# 2017_Ozone.net
KiCad netlist of a schematic drawn in Altium Designer
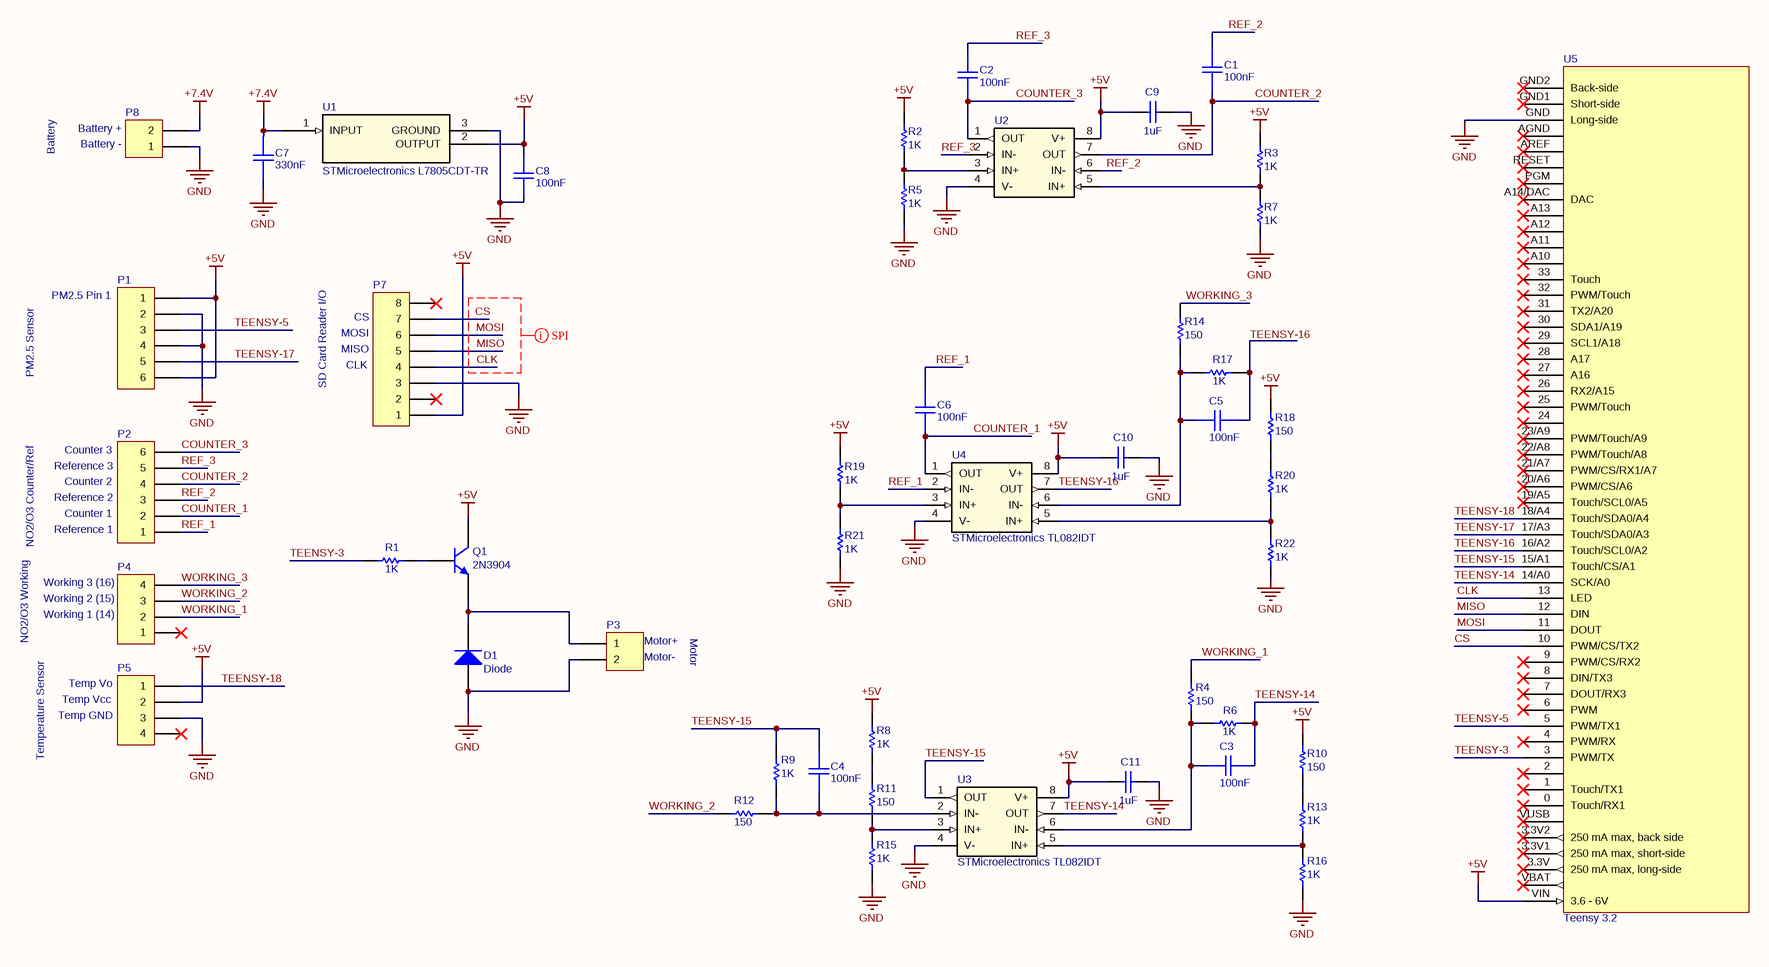
[diagram p0: 2017_Ozone.SchDoc]

(export (version "E")
  (design (tool "Eeschema 10.0.6"))
  (components
    (comp (ref "C1")
      (value "100nF")
      (footprint "Yageo CC0603ZRY5V9BB104 (1608)")
      (description "100 nF Capacitor")
      (fields (field (name "MANUFACTURER_PART_NUMBER") "CC0603ZRY5V9BB104"))
      (libsource (lib "2017_Ozone") (part "Yageo CC0603ZRY5V9BB104"))
    )
    (comp (ref "C2")
      (value "100nF")
      (footprint "Yageo CC0603ZRY5V9BB104 (1608)")
      (description "100 nF Capacitor")
      (fields (field (name "MANUFACTURER_PART_NUMBER") "CC0603ZRY5V9BB104"))
      (libsource (lib "2017_Ozone") (part "Yageo CC0603ZRY5V9BB104"))
    )
    (comp (ref "C3")
      (value "100nF")
      (footprint "Yageo CC0603ZRY5V9BB104 (1608)")
      (description "100 nF Capacitor")
      (fields (field (name "MANUFACTURER_PART_NUMBER") "CC0603ZRY5V9BB104"))
      (libsource (lib "2017_Ozone") (part "Yageo CC0603ZRY5V9BB104"))
    )
    (comp (ref "C4")
      (value "100nF")
      (footprint "Yageo CC0603ZRY5V9BB104 (1608)")
      (description "100 nF Capacitor")
      (fields (field (name "MANUFACTURER_PART_NUMBER") "CC0603ZRY5V9BB104"))
      (libsource (lib "2017_Ozone") (part "Yageo CC0603ZRY5V9BB104"))
    )
    (comp (ref "C5")
      (value "100nF")
      (footprint "Yageo CC0603ZRY5V9BB104 (1608)")
      (description "100 nF Capacitor")
      (fields (field (name "MANUFACTURER_PART_NUMBER") "CC0603ZRY5V9BB104"))
      (libsource (lib "2017_Ozone") (part "Yageo CC0603ZRY5V9BB104"))
    )
    (comp (ref "C6")
      (value "100nF")
      (footprint "Yageo CC0603ZRY5V9BB104 (1608)")
      (description "100 nF Capacitor")
      (fields (field (name "MANUFACTURER_PART_NUMBER") "CC0603ZRY5V9BB104"))
      (libsource (lib "2017_Ozone") (part "Yageo CC0603ZRY5V9BB104"))
    )
    (comp (ref "C7")
      (value "330nF")
      (footprint "Yageo CC0603ZRY5V9BB104 (1608)")
      (description "330nF Capacitor")
      (libsource (lib "") (part "Yageo CC0603ZRY5V9BB104_1"))
    )
    (comp (ref "C8")
      (value "100nF")
      (footprint "Yageo CC0603ZRY5V9BB104 (1608)")
      (description "100 nF Capacitor")
      (fields (field (name "MANUFACTURER_PART_NUMBER") "CC0603ZRY5V9BB104"))
      (libsource (lib "") (part "Yageo CC0603ZRY5V9BB104_1"))
    )
    (comp (ref "C9")
      (value "1uF")
      (footprint "Yageo CC0603ZRY5V9BB104 (1608)")
      (description "Capacitor")
      (fields (field (name "Comment") "Cap") (field (name "PUBLISHER") "Altium Limited"))
      (libsource (lib "Miscellaneous Devices") (part "Cap"))
    )
    (comp (ref "C10")
      (value "1uF")
      (footprint "Yageo CC0603ZRY5V9BB104 (1608)")
      (description "Capacitor")
      (fields (field (name "Comment") "Cap") (field (name "PUBLISHER") "Altium Limited"))
      (libsource (lib "Miscellaneous Devices") (part "Cap"))
    )
    (comp (ref "C11")
      (value "1uF")
      (footprint "Yageo CC0603ZRY5V9BB104 (1608)")
      (description "Capacitor")
      (fields (field (name "Comment") "Cap") (field (name "PUBLISHER") "Altium Limited"))
      (libsource (lib "Miscellaneous Devices") (part "Cap"))
    )
    (comp (ref "D1")
      (value "Diode")
      (footprint "SOT95P240X120-3N")
      (description "Default Diode")
      (fields (field (name "PUBLISHER") "Altium Limited"))
      (libsource (lib "Miscellaneous Devices") (part "Diode"))
    )
    (comp (ref "P1")
      (value "Molex 0430450600")
      (footprint "Molex 0430450600")
      (libsource (lib "") (part "Molex 0430450600_1"))
    )
    (comp (ref "P2")
      (value "Molex 0430450600")
      (footprint "Molex 0430450600")
      (libsource (lib "2017_Ozone") (part "Molex 0430450600"))
    )
    (comp (ref "P3")
      (value "Molex 0430450200")
      (footprint "Molex 0430450200")
      (libsource (lib "2017_Ozone") (part "Molex 0430450200"))
    )
    (comp (ref "P4")
      (value "Molex 0430450400")
      (footprint "Molex 0430450400")
      (libsource (lib "") (part "Molex 0430450400_1"))
    )
    (comp (ref "P5")
      (value "Molex 0430450400")
      (footprint "Molex 0430450400")
      (libsource (lib "2017_Ozone") (part "Molex 0430450400"))
    )
    (comp (ref "P7")
      (value "Molex 0430450800")
      (footprint "Molex 0430450800")
      (libsource (lib "2017_Ozone") (part "Molex 0430450800"))
    )
    (comp (ref "P8")
      (value "Molex 0430450200")
      (footprint "Molex 0430450200")
      (libsource (lib "") (part "Molex 0430450200_1"))
    )
    (comp (ref "Q1")
      (value "2N3904")
      (footprint "TO92")
      (description "NPN General Purpose Amplifier")
      (fields (field (name "PUBLISHER") "Altium Limited"))
      (libsource (lib "Miscellaneous Devices") (part "2N3904"))
    )
    (comp (ref "R1")
      (value "1K")
      (footprint "Panasonic ERJ-Series (1608)")
      (description "Resistor")
      (fields (field (name "Comment") "1k Ohm") (field (name "PUBLISHER") "Altium Limited"))
      (libsource (lib "") (part "1k Ohm_1"))
    )
    (comp (ref "R2")
      (value "1K")
      (footprint "Panasonic ERJ-Series (1608)")
      (description "Resistor")
      (fields (field (name "Comment") "1k Ohm") (field (name "PUBLISHER") "Altium Limited"))
      (libsource (lib "2017_Ozone") (part "1k Ohm"))
    )
    (comp (ref "R3")
      (value "1K")
      (footprint "Panasonic ERJ-Series (1608)")
      (description "Resistor")
      (fields (field (name "Comment") "1k Ohm") (field (name "PUBLISHER") "Altium Limited"))
      (libsource (lib "2017_Ozone") (part "1k Ohm"))
    )
    (comp (ref "R4")
      (value "150")
      (footprint "Panasonic ERJ-Series (1608)")
      (description "Resistor")
      (fields (field (name "Comment") "150 Ohm") (field (name "PUBLISHER") "Altium Limited"))
      (libsource (lib "2017_Ozone") (part "150 Ohm"))
    )
    (comp (ref "R5")
      (value "1K")
      (footprint "Panasonic ERJ-Series (1608)")
      (description "Resistor")
      (fields (field (name "Comment") "1k Ohm") (field (name "PUBLISHER") "Altium Limited"))
      (libsource (lib "2017_Ozone") (part "1k Ohm"))
    )
    (comp (ref "R6")
      (value "1K")
      (footprint "Panasonic ERJ-Series (1608)")
      (description "Resistor")
      (fields (field (name "Comment") "1k Ohm") (field (name "PUBLISHER") "Altium Limited"))
      (libsource (lib "2017_Ozone") (part "1k Ohm"))
    )
    (comp (ref "R7")
      (value "1K")
      (footprint "Panasonic ERJ-Series (1608)")
      (description "Resistor")
      (fields (field (name "Comment") "1k Ohm") (field (name "PUBLISHER") "Altium Limited"))
      (libsource (lib "2017_Ozone") (part "1k Ohm"))
    )
    (comp (ref "R8")
      (value "1K")
      (footprint "Panasonic ERJ-Series (1608)")
      (description "1k Ohm Resistor")
      (fields (field (name "Comment") "Panasonic ERJ-3GEYJ102V") (field (name "PUBLISHER") "Altium Limited"))
      (libsource (lib "2017_Ozone") (part "Panasonic ERJ-3GEYJ102V"))
    )
    (comp (ref "R9")
      (value "1K")
      (footprint "Panasonic ERJ-Series (1608)")
      (description "Resistor")
      (fields (field (name "Comment") "1k Ohm") (field (name "PUBLISHER") "Altium Limited"))
      (libsource (lib "2017_Ozone") (part "1k Ohm"))
    )
    (comp (ref "R10")
      (value "150")
      (footprint "Panasonic ERJ-Series (1608)")
      (description "Resistor")
      (fields (field (name "Comment") "150 Ohm") (field (name "PUBLISHER") "Altium Limited"))
      (libsource (lib "2017_Ozone") (part "150 Ohm"))
    )
    (comp (ref "R11")
      (value "150")
      (footprint "Panasonic ERJ-Series (1608)")
      (description "150 Ohm Resistor")
      (fields (field (name "Comment") "150 Ohm") (field (name "PUBLISHER") "Altium Limited"))
      (libsource (lib "") (part "150 Ohm_1"))
    )
    (comp (ref "R12")
      (value "150")
      (footprint "Panasonic ERJ-Series (1608)")
      (description "Resistor")
      (fields (field (name "Comment") "150 Ohm") (field (name "PUBLISHER") "Altium Limited"))
      (libsource (lib "2017_Ozone") (part "150 Ohm"))
    )
    (comp (ref "R13")
      (value "1K")
      (footprint "Panasonic ERJ-Series (1608)")
      (description "Resistor")
      (fields (field (name "Comment") "1k Ohm") (field (name "PUBLISHER") "Altium Limited"))
      (libsource (lib "2017_Ozone") (part "1k Ohm"))
    )
    (comp (ref "R14")
      (value "150")
      (footprint "Panasonic ERJ-Series (1608)")
      (description "Resistor")
      (fields (field (name "Comment") "150 Ohm") (field (name "PUBLISHER") "Altium Limited"))
      (libsource (lib "2017_Ozone") (part "150 Ohm"))
    )
    (comp (ref "R15")
      (value "1K")
      (footprint "Panasonic ERJ-Series (1608)")
      (description "Resistor")
      (fields (field (name "Comment") "1k Ohm") (field (name "PUBLISHER") "Altium Limited"))
      (libsource (lib "2017_Ozone") (part "1k Ohm"))
    )
    (comp (ref "R16")
      (value "1K")
      (footprint "Panasonic ERJ-Series (1608)")
      (description "Resistor")
      (fields (field (name "Comment") "1k Ohm") (field (name "PUBLISHER") "Altium Limited"))
      (libsource (lib "2017_Ozone") (part "1k Ohm"))
    )
    (comp (ref "R17")
      (value "1K")
      (footprint "Panasonic ERJ-Series (1608)")
      (description "Resistor")
      (fields (field (name "Comment") "1k Ohm") (field (name "PUBLISHER") "Altium Limited"))
      (libsource (lib "2017_Ozone") (part "1k Ohm"))
    )
    (comp (ref "R18")
      (value "150")
      (footprint "Panasonic ERJ-Series (1608)")
      (description "Resistor")
      (fields (field (name "Comment") "150 Ohm") (field (name "PUBLISHER") "Altium Limited"))
      (libsource (lib "2017_Ozone") (part "150 Ohm"))
    )
    (comp (ref "R19")
      (value "1K")
      (footprint "Panasonic ERJ-Series (1608)")
      (description "Resistor")
      (fields (field (name "Comment") "1k Ohm") (field (name "PUBLISHER") "Altium Limited"))
      (libsource (lib "2017_Ozone") (part "1k Ohm"))
    )
    (comp (ref "R20")
      (value "1K")
      (footprint "Panasonic ERJ-Series (1608)")
      (description "1k Ohm Resistor")
      (fields (field (name "Comment") "Panasonic ERJ-3GEYJ102V") (field (name "PUBLISHER") "Altium Limited"))
      (libsource (lib "2017_Ozone") (part "Panasonic ERJ-3GEYJ102V"))
    )
    (comp (ref "R21")
      (value "1K")
      (footprint "Panasonic ERJ-Series (1608)")
      (description "Resistor")
      (fields (field (name "Comment") "1k Ohm") (field (name "PUBLISHER") "Altium Limited"))
      (libsource (lib "2017_Ozone") (part "1k Ohm"))
    )
    (comp (ref "R22")
      (value "1K")
      (footprint "Panasonic ERJ-Series (1608)")
      (description "Resistor")
      (fields (field (name "Comment") "1k Ohm") (field (name "PUBLISHER") "Altium Limited"))
      (libsource (lib "2017_Ozone") (part "1k Ohm"))
    )
    (comp (ref "U1")
      (value "STMicroelectronics L7805CDT-TR")
      (footprint "STMicroelectronics L7805CDT-TR")
      (description "Linear Voltage Regulator IC Positive Fixed Output 5V 1.5A D-Pak")
      (libsource (lib "2017_Ozone") (part "STMicroelectronics L7805CDT-TR"))
    )
    (comp (ref "U2")
      (value "STMicroelectronics TL082IDT")
      (footprint "STMicroelectronics TL082IDT (8-SOIC)")
      (description "IC OPAMP JFET 4MHZ 8SO")
      (libsource (lib "2017_Ozone") (part "STMicroelectronics TL082IDT"))
    )
    (comp (ref "U3")
      (value "STMicroelectronics TL082IDT")
      (footprint "STMicroelectronics TL082IDT (8-SOIC)")
      (description "IC OPAMP JFET 4MHZ 8SO")
      (libsource (lib "2017_Ozone") (part "STMicroelectronics TL082IDT"))
    )
    (comp (ref "U4")
      (value "STMicroelectronics TL082IDT")
      (footprint "STMicroelectronics TL082IDT (8-SOIC)")
      (description "IC OPAMP JFET 4MHZ 8SO")
      (libsource (lib "2017_Ozone") (part "STMicroelectronics TL082IDT"))
    )
    (comp (ref "U5")
      (value "Teensy 3.2")
      (footprint "PJRC TEENSY 3.2")
      (description "Teensy 3.2 Development Board")
      (libsource (lib "2017_Ozone") (part "PJRC Teensy 3.2"))
    )
  )
  (nets
    (net (code "1") (name "+5V") (class "Default")
      (node (ref "C10") (pin "1") (pinfunction "1_1") (pintype "passive"))
      (node (ref "C11") (pin "1") (pinfunction "1_1") (pintype "passive"))
      (node (ref "C8") (pin "2") (pinfunction "2_2") (pintype "passive"))
      (node (ref "C9") (pin "1") (pinfunction "1_1") (pintype "passive"))
      (node (ref "P1") (pin "1") (pinfunction "1_1") (pintype "passive"))
      (node (ref "P1") (pin "6") (pinfunction "6_6") (pintype "passive"))
      (node (ref "P5") (pin "2") (pinfunction "2_2") (pintype "passive"))
      (node (ref "P7") (pin "1") (pinfunction "1_1") (pintype "passive"))
      (node (ref "Q1") (pin "3") (pinfunction "C_3") (pintype "passive"))
      (node (ref "R10") (pin "1") (pinfunction "1_1") (pintype "passive"))
      (node (ref "R18") (pin "2") (pinfunction "2_2") (pintype "passive"))
      (node (ref "R19") (pin "1") (pinfunction "1_1") (pintype "passive"))
      (node (ref "R2") (pin "1") (pinfunction "1_1") (pintype "passive"))
      (node (ref "R3") (pin "1") (pinfunction "1_1") (pintype "passive"))
      (node (ref "R8") (pin "1") (pinfunction "1_1") (pintype "passive"))
      (node (ref "U1") (pin "2") (pinfunction "OUTPUT_2") (pintype "passive"))
      (node (ref "U2") (pin "8") (pinfunction "V+_8") (pintype "power_in"))
      (node (ref "U3") (pin "8") (pinfunction "V+_8") (pintype "power_in"))
      (node (ref "U4") (pin "8") (pinfunction "V+_8") (pintype "power_in"))
      (node (ref "U5") (pin "VIN") (pinfunction "3.6_-_6V_VIN") (pintype "input"))
    )
    (net (code "2") (name "+7.4V") (class "Default")
      (node (ref "C7") (pin "2") (pinfunction "2_2") (pintype "passive"))
      (node (ref "P8") (pin "2") (pinfunction "2_2") (pintype "passive"))
      (node (ref "U1") (pin "1") (pinfunction "INPUT_1") (pintype "input"))
    )
    (net (code "3") (name "/CLK") (class "Default")
      (node (ref "P7") (pin "4") (pinfunction "4_4") (pintype "passive"))
      (node (ref "U5") (pin "13") (pinfunction "LED_13") (pintype "passive"))
    )
    (net (code "4") (name "/COUNTER_1") (class "Default")
      (node (ref "C6") (pin "1") (pinfunction "1_1") (pintype "passive"))
      (node (ref "P2") (pin "2") (pinfunction "2_2") (pintype "passive"))
      (node (ref "U4") (pin "1") (pinfunction "OUT_1") (pintype "output"))
    )
    (net (code "5") (name "/COUNTER_2") (class "Default")
      (node (ref "C1") (pin "1") (pinfunction "1_1") (pintype "passive"))
      (node (ref "P2") (pin "4") (pinfunction "4_4") (pintype "passive"))
      (node (ref "U2") (pin "7") (pinfunction "OUT_7") (pintype "output"))
    )
    (net (code "6") (name "/COUNTER_3") (class "Default")
      (node (ref "C2") (pin "1") (pinfunction "1_1") (pintype "passive"))
      (node (ref "P2") (pin "6") (pinfunction "6_6") (pintype "passive"))
      (node (ref "U2") (pin "1") (pinfunction "OUT_1") (pintype "output"))
    )
    (net (code "7") (name "/CS") (class "Default")
      (node (ref "P7") (pin "7") (pinfunction "7_7") (pintype "passive"))
      (node (ref "U5") (pin "10") (pinfunction "PWM/CS/TX2_10") (pintype "passive"))
    )
    (net (code "8") (name "/MISO") (class "Default")
      (node (ref "P7") (pin "5") (pinfunction "5_5") (pintype "passive"))
      (node (ref "U5") (pin "12") (pinfunction "DIN_12") (pintype "passive"))
    )
    (net (code "9") (name "/MOSI") (class "Default")
      (node (ref "P7") (pin "6") (pinfunction "6_6") (pintype "passive"))
      (node (ref "U5") (pin "11") (pinfunction "DOUT_11") (pintype "passive"))
    )
    (net (code "10") (name "/REF_1") (class "Default")
      (node (ref "C6") (pin "2") (pinfunction "2_2") (pintype "passive"))
      (node (ref "P2") (pin "1") (pinfunction "1_1") (pintype "passive"))
      (node (ref "U4") (pin "2") (pinfunction "IN-_2") (pintype "input"))
    )
    (net (code "11") (name "/REF_2") (class "Default")
      (node (ref "C1") (pin "2") (pinfunction "2_2") (pintype "passive"))
      (node (ref "P2") (pin "3") (pinfunction "3_3") (pintype "passive"))
      (node (ref "U2") (pin "6") (pinfunction "IN-_6") (pintype "input"))
    )
    (net (code "12") (name "/REF_3") (class "Default")
      (node (ref "C2") (pin "2") (pinfunction "2_2") (pintype "passive"))
      (node (ref "P2") (pin "5") (pinfunction "5_5") (pintype "passive"))
      (node (ref "U2") (pin "2") (pinfunction "IN-_2") (pintype "input"))
    )
    (net (code "13") (name "/TEENSY-3") (class "Default")
      (node (ref "R1") (pin "1") (pinfunction "1_1") (pintype "passive"))
      (node (ref "U5") (pin "3") (pinfunction "PWM/TX_3") (pintype "passive"))
    )
    (net (code "14") (name "/TEENSY-5") (class "Default")
      (node (ref "P1") (pin "3") (pinfunction "3_3") (pintype "passive"))
      (node (ref "U5") (pin "5") (pinfunction "PWM/TX1_5") (pintype "passive"))
    )
    (net (code "15") (name "/TEENSY-14") (class "Default")
      (node (ref "C3") (pin "2") (pinfunction "2_2") (pintype "passive"))
      (node (ref "R6") (pin "2") (pinfunction "2_2") (pintype "passive"))
      (node (ref "U3") (pin "7") (pinfunction "OUT_7") (pintype "output"))
      (node (ref "U5") (pin "14/A0") (pinfunction "SCK/A0_14/A0") (pintype "passive"))
    )
    (net (code "16") (name "/TEENSY-15") (class "Default")
      (node (ref "C4") (pin "2") (pinfunction "2_2") (pintype "passive"))
      (node (ref "R9") (pin "2") (pinfunction "2_2") (pintype "passive"))
      (node (ref "U3") (pin "1") (pinfunction "OUT_1") (pintype "output"))
      (node (ref "U5") (pin "15/A1") (pinfunction "Touch/CS/A1_15/A1") (pintype "passive"))
    )
    (net (code "17") (name "/TEENSY-16") (class "Default")
      (node (ref "C5") (pin "2") (pinfunction "2_2") (pintype "passive"))
      (node (ref "R17") (pin "2") (pinfunction "2_2") (pintype "passive"))
      (node (ref "U4") (pin "7") (pinfunction "OUT_7") (pintype "output"))
      (node (ref "U5") (pin "16/A2") (pinfunction "Touch/SCL0/A2_16/A2") (pintype "passive"))
    )
    (net (code "18") (name "/TEENSY-17") (class "Default")
      (node (ref "P1") (pin "5") (pinfunction "5_5") (pintype "passive"))
      (node (ref "U5") (pin "17/A3") (pinfunction "Touch/SDA0/A3_17/A3") (pintype "passive"))
    )
    (net (code "19") (name "/TEENSY-18") (class "Default")
      (node (ref "P5") (pin "1") (pinfunction "1_1") (pintype "passive"))
      (node (ref "U5") (pin "18/A4") (pinfunction "Touch/SDA0/A4_18/A4") (pintype "passive"))
    )
    (net (code "20") (name "/WORKING_1") (class "Default")
      (node (ref "P4") (pin "2") (pinfunction "2_2") (pintype "passive"))
      (node (ref "R4") (pin "2") (pinfunction "2_2") (pintype "passive"))
    )
    (net (code "21") (name "/WORKING_2") (class "Default")
      (node (ref "P4") (pin "3") (pinfunction "3_3") (pintype "passive"))
      (node (ref "R12") (pin "2") (pinfunction "2_2") (pintype "passive"))
    )
    (net (code "22") (name "/WORKING_3") (class "Default")
      (node (ref "P4") (pin "4") (pinfunction "4_4") (pintype "passive"))
      (node (ref "R14") (pin "2") (pinfunction "2_2") (pintype "passive"))
    )
    (net (code "23") (name "GND") (class "Default")
      (node (ref "C10") (pin "2") (pinfunction "2_2") (pintype "passive"))
      (node (ref "C11") (pin "2") (pinfunction "2_2") (pintype "passive"))
      (node (ref "C7") (pin "1") (pinfunction "1_1") (pintype "passive"))
      (node (ref "C8") (pin "1") (pinfunction "1_1") (pintype "passive"))
      (node (ref "C9") (pin "2") (pinfunction "2_2") (pintype "passive"))
      (node (ref "D1") (pin "1") (pinfunction "A_1") (pintype "passive"))
      (node (ref "P1") (pin "2") (pinfunction "2_2") (pintype "passive"))
      (node (ref "P1") (pin "4") (pinfunction "4_4") (pintype "passive"))
      (node (ref "P3") (pin "2") (pinfunction "2_2") (pintype "passive"))
      (node (ref "P5") (pin "3") (pinfunction "3_3") (pintype "passive"))
      (node (ref "P7") (pin "3") (pinfunction "3_3") (pintype "passive"))
      (node (ref "P8") (pin "1") (pinfunction "1_1") (pintype "passive"))
      (node (ref "R15") (pin "1") (pinfunction "1_1") (pintype "passive"))
      (node (ref "R16") (pin "1") (pinfunction "1_1") (pintype "passive"))
      (node (ref "R21") (pin "2") (pinfunction "2_2") (pintype "passive"))
      (node (ref "R22") (pin "2") (pinfunction "2_2") (pintype "passive"))
      (node (ref "R5") (pin "2") (pinfunction "2_2") (pintype "passive"))
      (node (ref "R7") (pin "2") (pinfunction "2_2") (pintype "passive"))
      (node (ref "U1") (pin "3") (pinfunction "GROUND_3") (pintype "passive"))
      (node (ref "U2") (pin "4") (pinfunction "V-_4") (pintype "power_in"))
      (node (ref "U3") (pin "4") (pinfunction "V-_4") (pintype "power_in"))
      (node (ref "U4") (pin "4") (pinfunction "V-_4") (pintype "power_in"))
      (node (ref "U5") (pin "GND") (pinfunction "Long-side_GND") (pintype "passive"))
    )
    (net (code "24") (name "Net-(C3-Pad1)") (class "Default")
      (node (ref "C3") (pin "1") (pinfunction "1_1") (pintype "passive"))
      (node (ref "R4") (pin "1") (pinfunction "1_1") (pintype "passive"))
      (node (ref "R6") (pin "1") (pinfunction "1_1") (pintype "passive"))
      (node (ref "U3") (pin "6") (pinfunction "IN-_6") (pintype "input"))
    )
    (net (code "25") (name "Net-(C4-Pad1)") (class "Default")
      (node (ref "C4") (pin "1") (pinfunction "1_1") (pintype "passive"))
      (node (ref "R12") (pin "1") (pinfunction "1_1") (pintype "passive"))
      (node (ref "R9") (pin "1") (pinfunction "1_1") (pintype "passive"))
      (node (ref "U3") (pin "2") (pinfunction "IN-_2") (pintype "input"))
    )
    (net (code "26") (name "Net-(C5-Pad1)") (class "Default")
      (node (ref "C5") (pin "1") (pinfunction "1_1") (pintype "passive"))
      (node (ref "R14") (pin "1") (pinfunction "1_1") (pintype "passive"))
      (node (ref "R17") (pin "1") (pinfunction "1_1") (pintype "passive"))
      (node (ref "U4") (pin "6") (pinfunction "IN-_6") (pintype "input"))
    )
    (net (code "27") (name "Net-(D1-K)") (class "Default")
      (node (ref "D1") (pin "2") (pinfunction "K_2") (pintype "passive"))
      (node (ref "P3") (pin "1") (pinfunction "1_1") (pintype "passive"))
      (node (ref "Q1") (pin "1") (pinfunction "E_1") (pintype "passive"))
    )
    (net (code "28") (name "Net-(Q1-B)") (class "Default")
      (node (ref "Q1") (pin "2") (pinfunction "B_2") (pintype "passive"))
      (node (ref "R1") (pin "2") (pinfunction "2_2") (pintype "passive"))
    )
    (net (code "29") (name "Net-(R2-Pad2)") (class "Default")
      (node (ref "R2") (pin "2") (pinfunction "2_2") (pintype "passive"))
      (node (ref "R5") (pin "1") (pinfunction "1_1") (pintype "passive"))
      (node (ref "U2") (pin "3") (pinfunction "IN+_3") (pintype "input"))
    )
    (net (code "30") (name "Net-(R3-Pad2)") (class "Default")
      (node (ref "R3") (pin "2") (pinfunction "2_2") (pintype "passive"))
      (node (ref "R7") (pin "1") (pinfunction "1_1") (pintype "passive"))
      (node (ref "U2") (pin "5") (pinfunction "IN+_5") (pintype "input"))
    )
    (net (code "31") (name "Net-(R10-Pad2)") (class "Default")
      (node (ref "R10") (pin "2") (pinfunction "2_2") (pintype "passive"))
      (node (ref "R13") (pin "2") (pinfunction "2_2") (pintype "passive"))
    )
    (net (code "32") (name "Net-(R11-Pad1)") (class "Default")
      (node (ref "R11") (pin "1") (pinfunction "1_1") (pintype "passive"))
      (node (ref "R15") (pin "2") (pinfunction "2_2") (pintype "passive"))
      (node (ref "U3") (pin "3") (pinfunction "IN+_3") (pintype "input"))
    )
    (net (code "33") (name "Net-(R11-Pad2)") (class "Default")
      (node (ref "R11") (pin "2") (pinfunction "2_2") (pintype "passive"))
      (node (ref "R8") (pin "2") (pinfunction "2_2") (pintype "passive"))
    )
    (net (code "34") (name "Net-(R13-Pad1)") (class "Default")
      (node (ref "R13") (pin "1") (pinfunction "1_1") (pintype "passive"))
      (node (ref "R16") (pin "2") (pinfunction "2_2") (pintype "passive"))
      (node (ref "U3") (pin "5") (pinfunction "IN+_5") (pintype "input"))
    )
    (net (code "35") (name "Net-(R18-Pad1)") (class "Default")
      (node (ref "R18") (pin "1") (pinfunction "1_1") (pintype "passive"))
      (node (ref "R20") (pin "1") (pinfunction "1_1") (pintype "passive"))
    )
    (net (code "36") (name "Net-(R19-Pad2)") (class "Default")
      (node (ref "R19") (pin "2") (pinfunction "2_2") (pintype "passive"))
      (node (ref "R21") (pin "1") (pinfunction "1_1") (pintype "passive"))
      (node (ref "U4") (pin "3") (pinfunction "IN+_3") (pintype "input"))
    )
    (net (code "37") (name "Net-(R20-Pad2)") (class "Default")
      (node (ref "R20") (pin "2") (pinfunction "2_2") (pintype "passive"))
      (node (ref "R22") (pin "1") (pinfunction "1_1") (pintype "passive"))
      (node (ref "U4") (pin "5") (pinfunction "IN+_5") (pintype "input"))
    )
    (net (code "38") (name "unconnected-(P4-Pad1)") (class "Default")
      (node (ref "P4") (pin "1") (pinfunction "1_1") (pintype "passive+no_connect"))
    )
    (net (code "39") (name "unconnected-(P5-Pad4)") (class "Default")
      (node (ref "P5") (pin "4") (pinfunction "4_4") (pintype "passive+no_connect"))
    )
    (net (code "40") (name "unconnected-(P7-Pad2)") (class "Default")
      (node (ref "P7") (pin "2") (pinfunction "2_2") (pintype "passive+no_connect"))
    )
    (net (code "41") (name "unconnected-(P7-Pad8)") (class "Default")
      (node (ref "P7") (pin "8") (pinfunction "8_8") (pintype "passive+no_connect"))
    )
    (net (code "42") (name "unconnected-(U5-250_mA_max,_back_side-Pad3.3V2)") (class "Default")
      (node (ref "U5") (pin "3.3V2") (pinfunction "250_mA_max,_back_side_3.3V2") (pintype "output+no_connect"))
    )
    (net (code "43") (name "unconnected-(U5-250_mA_max,_long-side-Pad3.3V)") (class "Default")
      (node (ref "U5") (pin "3.3V") (pinfunction "250_mA_max,_long-side_3.3V") (pintype "output+no_connect"))
    )
    (net (code "44") (name "unconnected-(U5-250_mA_max,_short-side-Pad3.3V1)") (class "Default")
      (node (ref "U5") (pin "3.3V1") (pinfunction "250_mA_max,_short-side_3.3V1") (pintype "output+no_connect"))
    )
    (net (code "45") (name "unconnected-(U5-A16-Pad27)") (class "Default")
      (node (ref "U5") (pin "27") (pinfunction "A16_27") (pintype "passive+no_connect"))
    )
    (net (code "46") (name "unconnected-(U5-A17-Pad28)") (class "Default")
      (node (ref "U5") (pin "28") (pinfunction "A17_28") (pintype "passive+no_connect"))
    )
    (net (code "47") (name "unconnected-(U5-Back-side-PadGND2)") (class "Default")
      (node (ref "U5") (pin "GND2") (pinfunction "Back-side_GND2") (pintype "passive+no_connect"))
    )
    (net (code "48") (name "unconnected-(U5-DAC-PadA14{slash}DAC)") (class "Default")
      (node (ref "U5") (pin "A14/DAC") (pinfunction "DAC_A14/DAC") (pintype "passive+no_connect"))
    )
    (net (code "49") (name "unconnected-(U5-DIN{slash}TX3-Pad8)") (class "Default")
      (node (ref "U5") (pin "8") (pinfunction "DIN/TX3_8") (pintype "passive+no_connect"))
    )
    (net (code "50") (name "unconnected-(U5-DOUT{slash}RX3-Pad7)") (class "Default")
      (node (ref "U5") (pin "7") (pinfunction "DOUT/RX3_7") (pintype "passive+no_connect"))
    )
    (net (code "51") (name "unconnected-(U5-PWM-Pad6)") (class "Default")
      (node (ref "U5") (pin "6") (pinfunction "PWM_6") (pintype "passive+no_connect"))
    )
    (net (code "52") (name "unconnected-(U5-PWM{slash}CS{slash}A6-Pad20{slash}A6)") (class "Default")
      (node (ref "U5") (pin "20/A6") (pinfunction "PWM/CS/A6_20/A6") (pintype "passive+no_connect"))
    )
    (net (code "53") (name "unconnected-(U5-PWM{slash}CS{slash}RX1{slash}A7-Pad21{slash}A7)") (class "Default")
      (node (ref "U5") (pin "21/A7") (pinfunction "PWM/CS/RX1/A7_21/A7") (pintype "passive+no_connect"))
    )
    (net (code "54") (name "unconnected-(U5-PWM{slash}CS{slash}RX2-Pad9)") (class "Default")
      (node (ref "U5") (pin "9") (pinfunction "PWM/CS/RX2_9") (pintype "passive+no_connect"))
    )
    (net (code "55") (name "unconnected-(U5-PWM{slash}RX-Pad4)") (class "Default")
      (node (ref "U5") (pin "4") (pinfunction "PWM/RX_4") (pintype "passive+no_connect"))
    )
    (net (code "56") (name "unconnected-(U5-PWM{slash}Touch-Pad25)") (class "Default")
      (node (ref "U5") (pin "25") (pinfunction "PWM/Touch_25") (pintype "passive+no_connect"))
    )
    (net (code "57") (name "unconnected-(U5-PWM{slash}Touch-Pad32)") (class "Default")
      (node (ref "U5") (pin "32") (pinfunction "PWM/Touch_32") (pintype "passive+no_connect"))
    )
    (net (code "58") (name "unconnected-(U5-PWM{slash}Touch{slash}A8-Pad22{slash}A8)") (class "Default")
      (node (ref "U5") (pin "22/A8") (pinfunction "PWM/Touch/A8_22/A8") (pintype "passive+no_connect"))
    )
    (net (code "59") (name "unconnected-(U5-PWM{slash}Touch{slash}A9-Pad23{slash}A9)") (class "Default")
      (node (ref "U5") (pin "23/A9") (pinfunction "PWM/Touch/A9_23/A9") (pintype "passive+no_connect"))
    )
    (net (code "60") (name "unconnected-(U5-Pad2)") (class "Default")
      (node (ref "U5") (pin "2") (pintype "passive+no_connect"))
    )
    (net (code "61") (name "unconnected-(U5-Pad24)") (class "Default")
      (node (ref "U5") (pin "24") (pintype "passive+no_connect"))
    )
    (net (code "62") (name "unconnected-(U5-PadA10)") (class "Default")
      (node (ref "U5") (pin "A10") (pintype "passive+no_connect"))
    )
    (net (code "63") (name "unconnected-(U5-PadA11)") (class "Default")
      (node (ref "U5") (pin "A11") (pintype "passive+no_connect"))
    )
    (net (code "64") (name "unconnected-(U5-PadA12)") (class "Default")
      (node (ref "U5") (pin "A12") (pintype "passive+no_connect"))
    )
    (net (code "65") (name "unconnected-(U5-PadA13)") (class "Default")
      (node (ref "U5") (pin "A13") (pintype "passive+no_connect"))
    )
    (net (code "66") (name "unconnected-(U5-PadAGND)") (class "Default")
      (node (ref "U5") (pin "AGND") (pintype "passive+no_connect"))
    )
    (net (code "67") (name "unconnected-(U5-PadAREF)") (class "Default")
      (node (ref "U5") (pin "AREF") (pintype "passive+no_connect"))
    )
    (net (code "68") (name "unconnected-(U5-PadPGM)") (class "Default")
      (node (ref "U5") (pin "PGM") (pintype "passive"))
    )
    (net (code "69") (name "unconnected-(U5-PadRESET)") (class "Default")
      (node (ref "U5") (pin "RESET") (pintype "passive+no_connect"))
    )
    (net (code "70") (name "unconnected-(U5-PadVBAT)") (class "Default")
      (node (ref "U5") (pin "VBAT") (pintype "output+no_connect"))
    )
    (net (code "71") (name "unconnected-(U5-PadVUSB)") (class "Default")
      (node (ref "U5") (pin "VUSB") (pintype "passive+no_connect"))
    )
    (net (code "72") (name "unconnected-(U5-RX2{slash}A15-Pad26)") (class "Default")
      (node (ref "U5") (pin "26") (pinfunction "RX2/A15_26") (pintype "passive+no_connect"))
    )
    (net (code "73") (name "unconnected-(U5-SCL1{slash}A18-Pad29)") (class "Default")
      (node (ref "U5") (pin "29") (pinfunction "SCL1/A18_29") (pintype "passive+no_connect"))
    )
    (net (code "74") (name "unconnected-(U5-SDA1{slash}A19-Pad30)") (class "Default")
      (node (ref "U5") (pin "30") (pinfunction "SDA1/A19_30") (pintype "passive+no_connect"))
    )
    (net (code "75") (name "unconnected-(U5-Short-side-PadGND1)") (class "Default")
      (node (ref "U5") (pin "GND1") (pinfunction "Short-side_GND1") (pintype "passive+no_connect"))
    )
    (net (code "76") (name "unconnected-(U5-TX2{slash}A20-Pad31)") (class "Default")
      (node (ref "U5") (pin "31") (pinfunction "TX2/A20_31") (pintype "passive+no_connect"))
    )
    (net (code "77") (name "unconnected-(U5-Touch-Pad33)") (class "Default")
      (node (ref "U5") (pin "33") (pinfunction "Touch_33") (pintype "passive+no_connect"))
    )
    (net (code "78") (name "unconnected-(U5-Touch{slash}RX1-Pad0)") (class "Default")
      (node (ref "U5") (pin "0") (pinfunction "Touch/RX1_0") (pintype "passive+no_connect"))
    )
    (net (code "79") (name "unconnected-(U5-Touch{slash}SCL0{slash}A5-Pad19{slash}A5)") (class "Default")
      (node (ref "U5") (pin "19/A5") (pinfunction "Touch/SCL0/A5_19/A5") (pintype "passive+no_connect"))
    )
    (net (code "80") (name "unconnected-(U5-Touch{slash}TX1-Pad1)") (class "Default")
      (node (ref "U5") (pin "1") (pinfunction "Touch/TX1_1") (pintype "passive+no_connect"))
    )
  )
)
